# PIC32Circuit.net
KiCad netlist of a schematic drawn in EAGLE
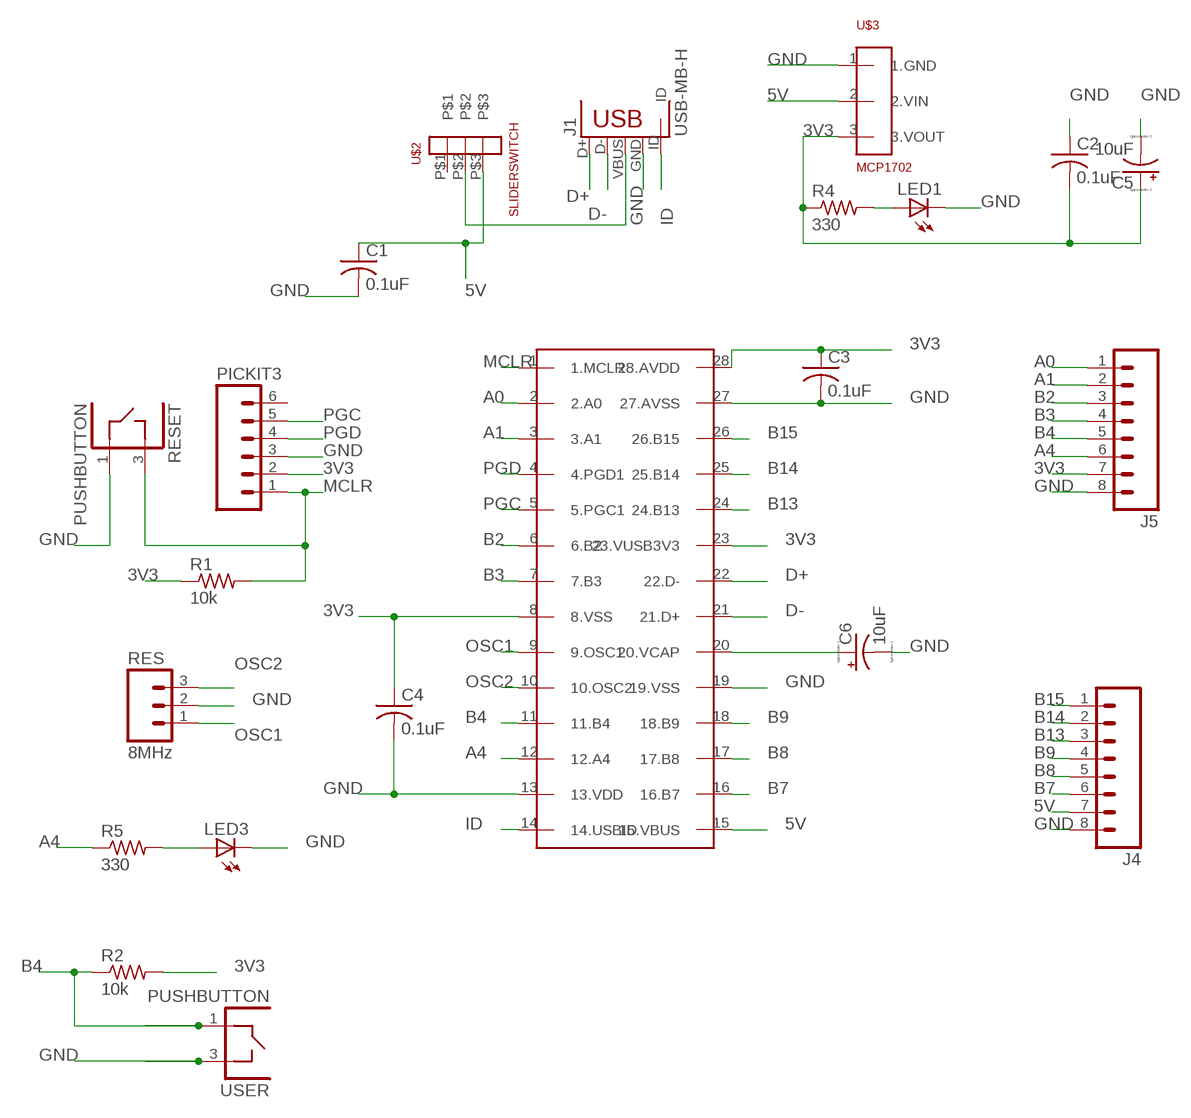
[diagram p0: schematic, sheet 1]

(export (version "E")
  (design (tool "Eeschema 10.0.6"))
  (components
    (comp (ref "C1")
      (value "0.1uF")
      (footprint "eagle-import:C025-024X044")
      (libsource (lib "eagle-import") (part "C-US025-024X044"))
    )
    (comp (ref "C2")
      (value "0.1uF")
      (footprint "eagle-import:C025-024X044")
      (libsource (lib "eagle-import") (part "C-US025-024X044"))
    )
    (comp (ref "C3")
      (value "0.1uF")
      (footprint "eagle-import:C025-024X044")
      (libsource (lib "eagle-import") (part "C-US025-024X044"))
    )
    (comp (ref "C4")
      (value "0.1uF")
      (footprint "eagle-import:C025-024X044")
      (libsource (lib "eagle-import") (part "C-US025-024X044"))
    )
    (comp (ref "C5")
      (value "10uF")
      (footprint "eagle-import:TT2D4")
      (libsource (lib "eagle-import") (part "CPOL-USTT2D4"))
    )
    (comp (ref "C6")
      (value "10uF")
      (footprint "eagle-import:TT2D4")
      (libsource (lib "eagle-import") (part "CPOL-USTT2D4"))
    )
    (comp (ref "J1")
      (value "USB-MB-H")
      (footprint "eagle-import:USB-MB-H")
      (libsource (lib "eagle-import") (part "USB-MB-H"))
    )
    (comp (ref "J4")
      (value "M08")
      (footprint "eagle-import:1X08_ROUND")
      (libsource (lib "eagle-import") (part "M08"))
    )
    (comp (ref "J5")
      (value "M08")
      (footprint "eagle-import:1X08_ROUND")
      (libsource (lib "eagle-import") (part "M08"))
    )
    (comp (ref "LED1")
      (value "LED3MM")
      (footprint "eagle-import:LED3MM")
      (libsource (lib "eagle-import") (part "LED3MM"))
    )
    (comp (ref "LED3")
      (value "LED3MM")
      (footprint "eagle-import:LED3MM")
      (libsource (lib "eagle-import") (part "LED3MM"))
    )
    (comp (ref "PICKIT3")
      (value "M06SILK_FEMALE_PTH")
      (footprint "eagle-import:1X06")
      (libsource (lib "eagle-import") (part "M06SILK_FEMALE_PTH"))
    )
    (comp (ref "R1")
      (value "10k")
      (footprint "eagle-import:0207_10")
      (libsource (lib "eagle-import") (part "R-US_0207/10"))
    )
    (comp (ref "R2")
      (value "10k")
      (footprint "eagle-import:0207_10")
      (libsource (lib "eagle-import") (part "R-US_0207/10"))
    )
    (comp (ref "R4")
      (value "330")
      (footprint "eagle-import:0207_10")
      (libsource (lib "eagle-import") (part "R-US_0207/10"))
    )
    (comp (ref "R5")
      (value "330")
      (footprint "eagle-import:0207_10")
      (libsource (lib "eagle-import") (part "R-US_0207/10"))
    )
    (comp (ref "RES")
      (value "8MHz")
      (footprint "eagle-import:1X03")
      (libsource (lib "eagle-import") (part "M03PTH"))
    )
    (comp (ref "RESET")
      (value "PUSHBUTTON")
      (footprint "eagle-import:PUSHBUTTON")
      (libsource (lib "eagle-import") (part "PUSHBUTTON"))
    )
    (comp (ref "U$1")
      (value "PIC32MX250F128B")
      (footprint "eagle-import:DIL28-3")
      (libsource (lib "eagle-import") (part "PIC32MX250F128B"))
    )
    (comp (ref "U$2")
      (value "SLIDERSWITCH")
      (footprint "eagle-import:SLIDERSWITCH")
      (libsource (lib "eagle-import") (part "SLIDERSWITCH"))
    )
    (comp (ref "U$3")
      (value "MCP1702")
      (footprint "eagle-import:TO92")
      (libsource (lib "eagle-import") (part "MCP1702"))
    )
    (comp (ref "USER")
      (value "PUSHBUTTON")
      (footprint "eagle-import:PUSHBUTTON")
      (libsource (lib "eagle-import") (part "PUSHBUTTON"))
    )
  )
  (nets
    (net (code "1") (name "/3V3") (class "Default")
      (node (ref "C2") (pin "2") (pinfunction "2_2") (pintype "passive"))
      (node (ref "C3") (pin "1") (pinfunction "1_1") (pintype "passive"))
      (node (ref "C4") (pin "1") (pinfunction "1_1") (pintype "passive"))
      (node (ref "C5") (pin "+") (pinfunction "+_+") (pintype "passive"))
      (node (ref "J5") (pin "7") (pinfunction "7_7") (pintype "passive"))
      (node (ref "PICKIT3") (pin "2") (pinfunction "2_2") (pintype "passive"))
      (node (ref "R1") (pin "1") (pinfunction "1_1") (pintype "passive"))
      (node (ref "R2") (pin "2") (pinfunction "2_2") (pintype "passive"))
      (node (ref "R4") (pin "1") (pinfunction "1_1") (pintype "passive"))
      (node (ref "U$1") (pin "23") (pinfunction "23.VUSB3V3_23") (pintype "bidirectional"))
      (node (ref "U$1") (pin "28") (pinfunction "28.AVDD_28") (pintype "bidirectional"))
      (node (ref "U$1") (pin "8") (pinfunction "8.VSS_8") (pintype "bidirectional"))
      (node (ref "U$3") (pin "3") (pinfunction "3.VOUT_3") (pintype "bidirectional"))
    )
    (net (code "2") (name "/5V") (class "Default")
      (node (ref "C1") (pin "1") (pinfunction "1_1") (pintype "passive"))
      (node (ref "J4") (pin "7") (pinfunction "7_7") (pintype "passive"))
      (node (ref "U$1") (pin "15") (pinfunction "15.VBUS_15") (pintype "bidirectional"))
      (node (ref "U$2") (pin "P$3") (pinfunction "P$3_P$3") (pintype "bidirectional"))
      (node (ref "U$3") (pin "2") (pinfunction "2.VIN_2") (pintype "bidirectional"))
    )
    (net (code "3") (name "/A0") (class "Default")
      (node (ref "J5") (pin "1") (pinfunction "1_1") (pintype "passive"))
      (node (ref "U$1") (pin "2") (pinfunction "2.A0_2") (pintype "bidirectional"))
    )
    (net (code "4") (name "/A1") (class "Default")
      (node (ref "J5") (pin "2") (pinfunction "2_2") (pintype "passive"))
      (node (ref "U$1") (pin "3") (pinfunction "3.A1_3") (pintype "bidirectional"))
    )
    (net (code "5") (name "/A4") (class "Default")
      (node (ref "J5") (pin "6") (pinfunction "6_6") (pintype "passive"))
      (node (ref "R5") (pin "1") (pinfunction "1_1") (pintype "passive"))
      (node (ref "U$1") (pin "12") (pinfunction "12.A4_12") (pintype "bidirectional"))
    )
    (net (code "6") (name "/B2") (class "Default")
      (node (ref "J5") (pin "3") (pinfunction "3_3") (pintype "passive"))
      (node (ref "U$1") (pin "6") (pinfunction "6.B2_6") (pintype "bidirectional"))
    )
    (net (code "7") (name "/B3") (class "Default")
      (node (ref "J5") (pin "4") (pinfunction "4_4") (pintype "passive"))
      (node (ref "U$1") (pin "7") (pinfunction "7.B3_7") (pintype "bidirectional"))
    )
    (net (code "8") (name "/B4") (class "Default")
      (node (ref "J5") (pin "5") (pinfunction "5_5") (pintype "passive"))
      (node (ref "R2") (pin "1") (pinfunction "1_1") (pintype "passive"))
      (node (ref "U$1") (pin "11") (pinfunction "11.B4_11") (pintype "bidirectional"))
      (node (ref "USER") (pin "1") (pinfunction "1_1") (pintype "passive"))
    )
    (net (code "9") (name "/B7") (class "Default")
      (node (ref "J4") (pin "6") (pinfunction "6_6") (pintype "passive"))
      (node (ref "U$1") (pin "16") (pinfunction "16.B7_16") (pintype "bidirectional"))
    )
    (net (code "10") (name "/B8") (class "Default")
      (node (ref "J4") (pin "5") (pinfunction "5_5") (pintype "passive"))
      (node (ref "U$1") (pin "17") (pinfunction "17.B8_17") (pintype "bidirectional"))
    )
    (net (code "11") (name "/B9") (class "Default")
      (node (ref "J4") (pin "4") (pinfunction "4_4") (pintype "passive"))
      (node (ref "U$1") (pin "18") (pinfunction "18.B9_18") (pintype "bidirectional"))
    )
    (net (code "12") (name "/B13") (class "Default")
      (node (ref "J4") (pin "3") (pinfunction "3_3") (pintype "passive"))
      (node (ref "U$1") (pin "24") (pinfunction "24.B13_24") (pintype "bidirectional"))
    )
    (net (code "13") (name "/B14") (class "Default")
      (node (ref "J4") (pin "2") (pinfunction "2_2") (pintype "passive"))
      (node (ref "U$1") (pin "25") (pinfunction "25.B14_25") (pintype "bidirectional"))
    )
    (net (code "14") (name "/B15") (class "Default")
      (node (ref "J4") (pin "1") (pinfunction "1_1") (pintype "passive"))
      (node (ref "U$1") (pin "26") (pinfunction "26.B15_26") (pintype "bidirectional"))
    )
    (net (code "15") (name "/D+") (class "Default")
      (node (ref "J1") (pin "D+") (pinfunction "D+_D+") (pintype "bidirectional"))
      (node (ref "U$1") (pin "22") (pinfunction "22.D-_22") (pintype "bidirectional"))
    )
    (net (code "16") (name "/D-") (class "Default")
      (node (ref "J1") (pin "D-") (pinfunction "D-_D-") (pintype "bidirectional"))
      (node (ref "U$1") (pin "21") (pinfunction "21.D+_21") (pintype "bidirectional"))
    )
    (net (code "17") (name "/GND") (class "Default")
      (node (ref "C1") (pin "2") (pinfunction "2_2") (pintype "passive"))
      (node (ref "C2") (pin "1") (pinfunction "1_1") (pintype "passive"))
      (node (ref "C3") (pin "2") (pinfunction "2_2") (pintype "passive"))
      (node (ref "C4") (pin "2") (pinfunction "2_2") (pintype "passive"))
      (node (ref "C5") (pin "-") (pinfunction "-_-") (pintype "passive"))
      (node (ref "C6") (pin "-") (pinfunction "-_-") (pintype "passive"))
      (node (ref "J1") (pin "GND") (pinfunction "GND_GND") (pintype "bidirectional"))
      (node (ref "J4") (pin "8") (pinfunction "8_8") (pintype "passive"))
      (node (ref "J5") (pin "8") (pinfunction "8_8") (pintype "passive"))
      (node (ref "LED1") (pin "K") (pinfunction "C_K") (pintype "passive"))
      (node (ref "LED3") (pin "K") (pinfunction "C_K") (pintype "passive"))
      (node (ref "PICKIT3") (pin "3") (pinfunction "3_3") (pintype "passive"))
      (node (ref "RES") (pin "2") (pinfunction "2_2") (pintype "passive"))
      (node (ref "RESET") (pin "1") (pinfunction "1_1") (pintype "passive"))
      (node (ref "U$1") (pin "13") (pinfunction "13.VDD_13") (pintype "bidirectional"))
      (node (ref "U$1") (pin "19") (pinfunction "19.VSS_19") (pintype "bidirectional"))
      (node (ref "U$1") (pin "27") (pinfunction "27.AVSS_27") (pintype "bidirectional"))
      (node (ref "U$3") (pin "1") (pinfunction "1.GND_1") (pintype "bidirectional"))
      (node (ref "USER") (pin "3") (pinfunction "3_3") (pintype "passive"))
    )
    (net (code "18") (name "/ID") (class "Default")
      (node (ref "J1") (pin "ID") (pinfunction "ID_ID") (pintype "bidirectional"))
      (node (ref "U$1") (pin "14") (pinfunction "14.USBID_14") (pintype "bidirectional"))
    )
    (net (code "19") (name "/MCLR") (class "Default")
      (node (ref "PICKIT3") (pin "1") (pinfunction "1_1") (pintype "passive"))
      (node (ref "R1") (pin "2") (pinfunction "2_2") (pintype "passive"))
      (node (ref "RESET") (pin "3") (pinfunction "3_3") (pintype "passive"))
      (node (ref "U$1") (pin "1") (pinfunction "1.MCLR_1") (pintype "bidirectional"))
    )
    (net (code "20") (name "/OSC1") (class "Default")
      (node (ref "RES") (pin "1") (pinfunction "1_1") (pintype "passive"))
      (node (ref "U$1") (pin "9") (pinfunction "9.OSC1_9") (pintype "bidirectional"))
    )
    (net (code "21") (name "/OSC2") (class "Default")
      (node (ref "RES") (pin "3") (pinfunction "3_3") (pintype "passive"))
      (node (ref "U$1") (pin "10") (pinfunction "10.OSC2_10") (pintype "bidirectional"))
    )
    (net (code "22") (name "/PGC") (class "Default")
      (node (ref "PICKIT3") (pin "5") (pinfunction "5_5") (pintype "passive"))
      (node (ref "U$1") (pin "5") (pinfunction "5.PGC1_5") (pintype "bidirectional"))
    )
    (net (code "23") (name "/PGD") (class "Default")
      (node (ref "PICKIT3") (pin "4") (pinfunction "4_4") (pintype "passive"))
      (node (ref "U$1") (pin "4") (pinfunction "4.PGD1_4") (pintype "bidirectional"))
    )
    (net (code "24") (name "Net-(J1-PadVBUS)") (class "Default")
      (node (ref "J1") (pin "VBUS") (pinfunction "VBUS_VBUS") (pintype "bidirectional"))
      (node (ref "U$2") (pin "P$2") (pinfunction "P$2_P$2") (pintype "bidirectional"))
    )
    (net (code "25") (name "Net-(LED1-PadA)") (class "Default")
      (node (ref "LED1") (pin "A") (pinfunction "A_A") (pintype "passive"))
      (node (ref "R4") (pin "2") (pinfunction "2_2") (pintype "passive"))
    )
    (net (code "26") (name "Net-(LED3-PadA)") (class "Default")
      (node (ref "LED3") (pin "A") (pinfunction "A_A") (pintype "passive"))
      (node (ref "R5") (pin "2") (pinfunction "2_2") (pintype "passive"))
    )
    (net (code "27") (name "Net-(U$1-20.VCAP)") (class "Default")
      (node (ref "C6") (pin "+") (pinfunction "+_+") (pintype "passive"))
      (node (ref "U$1") (pin "20") (pinfunction "20.VCAP_20") (pintype "bidirectional"))
    )
    (net (code "28") (name "unconnected-(PICKIT3-Pad6)") (class "Default")
      (node (ref "PICKIT3") (pin "6") (pinfunction "6_6") (pintype "passive"))
    )
    (net (code "29") (name "unconnected-(U$2-PadP$1)") (class "Default")
      (node (ref "U$2") (pin "P$1") (pinfunction "P$1_P$1") (pintype "bidirectional"))
    )
  )
)
